# SmartHomeRelaisAktor_0_1.net
KiCad netlist of a schematic drawn in EAGLE
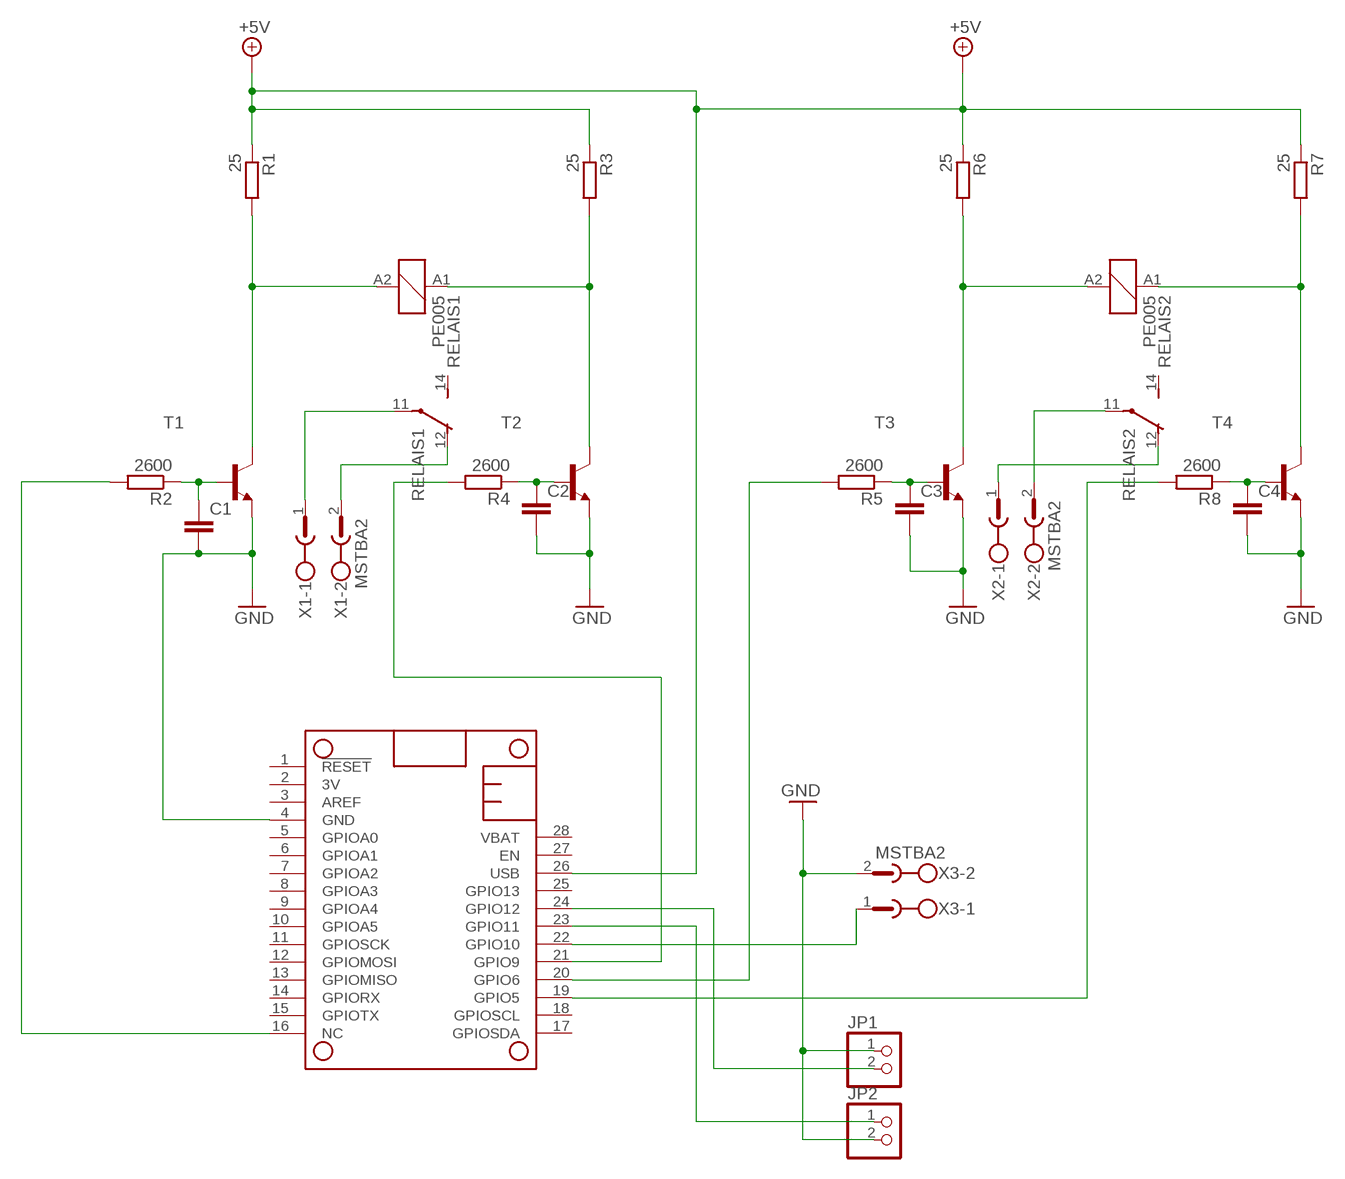
[diagram p0: schematic, sheet 1]

(export (version "E")
  (design (tool "Eeschema 10.0.6"))
  (components
    (comp (ref "C1")
      (value "C-EUC0805")
      (footprint "eagle-import:C0805")
      (libsource (lib "eagle-import") (part "C-EUC0805"))
    )
    (comp (ref "C2")
      (value "C-EUC0805")
      (footprint "eagle-import:C0805")
      (libsource (lib "eagle-import") (part "C-EUC0805"))
    )
    (comp (ref "C3")
      (value "C-EUC0805")
      (footprint "eagle-import:C0805")
      (libsource (lib "eagle-import") (part "C-EUC0805"))
    )
    (comp (ref "C4")
      (value "C-EUC0805")
      (footprint "eagle-import:C0805")
      (libsource (lib "eagle-import") (part "C-EUC0805"))
    )
    (comp (ref "JP1")
      (value "PINHD-1X2")
      (footprint "eagle-import:1X02")
      (libsource (lib "eagle-import") (part "PINHD-1X2"))
    )
    (comp (ref "JP2")
      (value "PINHD-1X2")
      (footprint "eagle-import:1X02")
      (libsource (lib "eagle-import") (part "PINHD-1X2"))
    )
    (comp (ref "MS1")
      (value "FEATHERWING")
      (footprint "eagle-import:FEATHERWING")
      (libsource (lib "eagle-import") (part "FEATHERWING"))
    )
    (comp (ref "R1")
      (value "25")
      (footprint "eagle-import:R0805")
      (libsource (lib "eagle-import") (part "R-EU_R0805"))
    )
    (comp (ref "R2")
      (value "2600")
      (footprint "eagle-import:R0805")
      (libsource (lib "eagle-import") (part "R-EU_R0805"))
    )
    (comp (ref "R3")
      (value "25")
      (footprint "eagle-import:R0805")
      (libsource (lib "eagle-import") (part "R-EU_R0805"))
    )
    (comp (ref "R4")
      (value "2600")
      (footprint "eagle-import:R0805")
      (libsource (lib "eagle-import") (part "R-EU_R0805"))
    )
    (comp (ref "R5")
      (value "2600")
      (footprint "eagle-import:R0805")
      (libsource (lib "eagle-import") (part "R-EU_R0805"))
    )
    (comp (ref "R6")
      (value "25")
      (footprint "eagle-import:R0805")
      (libsource (lib "eagle-import") (part "R-EU_R0805"))
    )
    (comp (ref "R7")
      (value "25")
      (footprint "eagle-import:R0805")
      (libsource (lib "eagle-import") (part "R-EU_R0805"))
    )
    (comp (ref "R8")
      (value "2600")
      (footprint "eagle-import:R0805")
      (libsource (lib "eagle-import") (part "R-EU_R0805"))
    )
    (comp (ref "RELAIS1")
      (value "PE005")
      (footprint "eagle-import:PE")
      (libsource (lib "eagle-import") (part "PE005"))
    )
    (comp (ref "RELAIS2")
      (value "PE005")
      (footprint "eagle-import:PE")
      (libsource (lib "eagle-import") (part "PE005"))
    )
    (comp (ref "T1")
      (value "BC817-16-NPN-SOT23-BEC")
      (footprint "eagle-import:SOT23-BEC")
      (libsource (lib "eagle-import") (part "-NPN-SOT23-BECBC817-16"))
    )
    (comp (ref "T2")
      (value "BC817-16-NPN-SOT23-BEC")
      (footprint "eagle-import:SOT23-BEC")
      (libsource (lib "eagle-import") (part "-NPN-SOT23-BECBC817-16"))
    )
    (comp (ref "T3")
      (value "BC817-16-NPN-SOT23-BEC")
      (footprint "eagle-import:SOT23-BEC")
      (libsource (lib "eagle-import") (part "-NPN-SOT23-BECBC817-16"))
    )
    (comp (ref "T4")
      (value "BC817-16-NPN-SOT23-BEC")
      (footprint "eagle-import:SOT23-BEC")
      (libsource (lib "eagle-import") (part "-NPN-SOT23-BECBC817-16"))
    )
    (comp (ref "X1")
      (value "MSTBA2")
      (footprint "eagle-import:MSTBA2")
      (fields (field (name "MF") "FARNELL") (field (name "MPN") "1757242"))
      (libsource (lib "eagle-import") (part "MSTBA2"))
    )
    (comp (ref "X2")
      (value "MSTBA2")
      (footprint "eagle-import:MSTBA2")
      (fields (field (name "MF") "FARNELL") (field (name "MPN") "1757242"))
      (libsource (lib "eagle-import") (part "MSTBA2"))
    )
    (comp (ref "X3")
      (value "MSTBA2")
      (footprint "eagle-import:MSTBA2")
      (fields (field (name "MF") "FARNELL") (field (name "MPN") "1757242"))
      (libsource (lib "eagle-import") (part "MSTBA2"))
    )
  )
  (nets
    (net (code "1") (name "+5V") (class "Default")
      (node (ref "MS1") (pin "26") (pinfunction "USB_26") (pintype "power_in"))
      (node (ref "R1") (pin "1") (pinfunction "1_1") (pintype "passive"))
      (node (ref "R3") (pin "1") (pinfunction "1_1") (pintype "passive"))
      (node (ref "R6") (pin "1") (pinfunction "1_1") (pintype "passive"))
      (node (ref "R7") (pin "1") (pinfunction "1_1") (pintype "passive"))
    )
    (net (code "2") (name "/3V") (class "Default")
      (node (ref "MS1") (pin "2") (pinfunction "3V_2") (pintype "power_in"))
    )
    (net (code "3") (name "/VBAT") (class "Default")
      (node (ref "MS1") (pin "28") (pinfunction "VBAT_28") (pintype "power_in"))
    )
    (net (code "4") (name "GND") (class "Default")
      (node (ref "C1") (pin "2") (pinfunction "2_2") (pintype "passive"))
      (node (ref "C2") (pin "2") (pinfunction "2_2") (pintype "passive"))
      (node (ref "C3") (pin "2") (pinfunction "2_2") (pintype "passive"))
      (node (ref "C4") (pin "2") (pinfunction "2_2") (pintype "passive"))
      (node (ref "JP1") (pin "1") (pinfunction "1_1") (pintype "passive"))
      (node (ref "JP2") (pin "2") (pinfunction "2_2") (pintype "passive"))
      (node (ref "MS1") (pin "4") (pinfunction "GND_4") (pintype "power_in"))
      (node (ref "T1") (pin "E") (pinfunction "E_E") (pintype "passive"))
      (node (ref "T2") (pin "E") (pinfunction "E_E") (pintype "passive"))
      (node (ref "T3") (pin "E") (pinfunction "E_E") (pintype "passive"))
      (node (ref "T4") (pin "E") (pinfunction "E_E") (pintype "passive"))
      (node (ref "X3") (pin "2") (pinfunction "1_2") (pintype "passive"))
    )
    (net (code "5") (name "Net-(C1-Pad1)") (class "Default")
      (node (ref "C1") (pin "1") (pinfunction "1_1") (pintype "passive"))
      (node (ref "R2") (pin "1") (pinfunction "1_1") (pintype "passive"))
      (node (ref "T1") (pin "B") (pinfunction "B_B") (pintype "passive"))
    )
    (net (code "6") (name "Net-(C2-Pad1)") (class "Default")
      (node (ref "C2") (pin "1") (pinfunction "1_1") (pintype "passive"))
      (node (ref "R4") (pin "1") (pinfunction "1_1") (pintype "passive"))
      (node (ref "T2") (pin "B") (pinfunction "B_B") (pintype "passive"))
    )
    (net (code "7") (name "Net-(C3-Pad1)") (class "Default")
      (node (ref "C3") (pin "1") (pinfunction "1_1") (pintype "passive"))
      (node (ref "R5") (pin "1") (pinfunction "1_1") (pintype "passive"))
      (node (ref "T3") (pin "B") (pinfunction "B_B") (pintype "passive"))
    )
    (net (code "8") (name "Net-(C4-Pad1)") (class "Default")
      (node (ref "C4") (pin "1") (pinfunction "1_1") (pintype "passive"))
      (node (ref "R8") (pin "1") (pinfunction "1_1") (pintype "passive"))
      (node (ref "T4") (pin "B") (pinfunction "B_B") (pintype "passive"))
    )
    (net (code "9") (name "Net-(MS1-GPIO5)") (class "Default")
      (node (ref "MS1") (pin "19") (pinfunction "GPIO5_19") (pintype "bidirectional"))
      (node (ref "R8") (pin "2") (pinfunction "2_2") (pintype "passive"))
    )
    (net (code "10") (name "Net-(MS1-GPIO6)") (class "Default")
      (node (ref "MS1") (pin "20") (pinfunction "GPIO6_20") (pintype "bidirectional"))
      (node (ref "R5") (pin "2") (pinfunction "2_2") (pintype "passive"))
    )
    (net (code "11") (name "Net-(MS1-GPIO9)") (class "Default")
      (node (ref "MS1") (pin "21") (pinfunction "GPIO9_21") (pintype "bidirectional"))
      (node (ref "R4") (pin "2") (pinfunction "2_2") (pintype "passive"))
    )
    (net (code "12") (name "Net-(MS1-GPIO10)") (class "Default")
      (node (ref "MS1") (pin "22") (pinfunction "GPIO10_22") (pintype "bidirectional"))
      (node (ref "X3") (pin "1") (pinfunction "1_1") (pintype "passive"))
    )
    (net (code "13") (name "Net-(MS1-GPIO11)") (class "Default")
      (node (ref "JP2") (pin "1") (pinfunction "1_1") (pintype "passive"))
      (node (ref "MS1") (pin "23") (pinfunction "GPIO11_23") (pintype "bidirectional"))
    )
    (net (code "14") (name "Net-(MS1-GPIO12)") (class "Default")
      (node (ref "JP1") (pin "2") (pinfunction "2_2") (pintype "passive"))
      (node (ref "MS1") (pin "24") (pinfunction "GPIO12_24") (pintype "bidirectional"))
    )
    (net (code "15") (name "Net-(MS1-NC)") (class "Default")
      (node (ref "MS1") (pin "16") (pinfunction "NC_16") (pintype "passive"))
      (node (ref "R2") (pin "2") (pinfunction "2_2") (pintype "passive"))
    )
    (net (code "16") (name "Net-(RELAIS1A-1)") (class "Default")
      (node (ref "R3") (pin "2") (pinfunction "2_2") (pintype "passive"))
      (node (ref "RELAIS1") (pin "A1") (pinfunction "1_A1") (pintype "passive"))
      (node (ref "T2") (pin "C") (pinfunction "C_C") (pintype "passive"))
    )
    (net (code "17") (name "Net-(RELAIS1A-2)") (class "Default")
      (node (ref "R1") (pin "2") (pinfunction "2_2") (pintype "passive"))
      (node (ref "RELAIS1") (pin "A2") (pinfunction "2_A2") (pintype "passive"))
      (node (ref "T1") (pin "C") (pinfunction "C_C") (pintype "passive"))
    )
    (net (code "18") (name "Net-(RELAIS1B-O)") (class "Default")
      (node (ref "RELAIS1") (pin "12") (pinfunction "O_12") (pintype "passive"))
      (node (ref "X1") (pin "2") (pinfunction "1_2") (pintype "passive"))
    )
    (net (code "19") (name "Net-(RELAIS1B-P)") (class "Default")
      (node (ref "RELAIS1") (pin "11") (pinfunction "P_11") (pintype "passive"))
      (node (ref "X1") (pin "1") (pinfunction "1_1") (pintype "passive"))
    )
    (net (code "20") (name "Net-(RELAIS2A-1)") (class "Default")
      (node (ref "R7") (pin "2") (pinfunction "2_2") (pintype "passive"))
      (node (ref "RELAIS2") (pin "A1") (pinfunction "1_A1") (pintype "passive"))
      (node (ref "T4") (pin "C") (pinfunction "C_C") (pintype "passive"))
    )
    (net (code "21") (name "Net-(RELAIS2A-2)") (class "Default")
      (node (ref "R6") (pin "2") (pinfunction "2_2") (pintype "passive"))
      (node (ref "RELAIS2") (pin "A2") (pinfunction "2_A2") (pintype "passive"))
      (node (ref "T3") (pin "C") (pinfunction "C_C") (pintype "passive"))
    )
    (net (code "22") (name "Net-(RELAIS2B-O)") (class "Default")
      (node (ref "RELAIS2") (pin "12") (pinfunction "O_12") (pintype "passive"))
      (node (ref "X2") (pin "1") (pinfunction "1_1") (pintype "passive"))
    )
    (net (code "23") (name "Net-(RELAIS2B-P)") (class "Default")
      (node (ref "RELAIS2") (pin "11") (pinfunction "P_11") (pintype "passive"))
      (node (ref "X2") (pin "2") (pinfunction "1_2") (pintype "passive"))
    )
    (net (code "24") (name "unconnected-(MS1-AREF-Pad3)") (class "Default")
      (node (ref "MS1") (pin "3") (pinfunction "AREF_3") (pintype "passive"))
    )
    (net (code "25") (name "unconnected-(MS1-EN-Pad27)") (class "Default")
      (node (ref "MS1") (pin "27") (pinfunction "EN_27") (pintype "passive"))
    )
    (net (code "26") (name "unconnected-(MS1-GPIO13-Pad25)") (class "Default")
      (node (ref "MS1") (pin "25") (pinfunction "GPIO13_25") (pintype "bidirectional"))
    )
    (net (code "27") (name "unconnected-(MS1-GPIOA0-Pad5)") (class "Default")
      (node (ref "MS1") (pin "5") (pinfunction "GPIOA0_5") (pintype "bidirectional"))
    )
    (net (code "28") (name "unconnected-(MS1-GPIOA1-Pad6)") (class "Default")
      (node (ref "MS1") (pin "6") (pinfunction "GPIOA1_6") (pintype "bidirectional"))
    )
    (net (code "29") (name "unconnected-(MS1-GPIOA2-Pad7)") (class "Default")
      (node (ref "MS1") (pin "7") (pinfunction "GPIOA2_7") (pintype "bidirectional"))
    )
    (net (code "30") (name "unconnected-(MS1-GPIOA3-Pad8)") (class "Default")
      (node (ref "MS1") (pin "8") (pinfunction "GPIOA3_8") (pintype "bidirectional"))
    )
    (net (code "31") (name "unconnected-(MS1-GPIOA4-Pad9)") (class "Default")
      (node (ref "MS1") (pin "9") (pinfunction "GPIOA4_9") (pintype "bidirectional"))
    )
    (net (code "32") (name "unconnected-(MS1-GPIOA5-Pad10)") (class "Default")
      (node (ref "MS1") (pin "10") (pinfunction "GPIOA5_10") (pintype "bidirectional"))
    )
    (net (code "33") (name "unconnected-(MS1-GPIOMISO-Pad13)") (class "Default")
      (node (ref "MS1") (pin "13") (pinfunction "GPIOMISO_13") (pintype "bidirectional"))
    )
    (net (code "34") (name "unconnected-(MS1-GPIOMOSI-Pad12)") (class "Default")
      (node (ref "MS1") (pin "12") (pinfunction "GPIOMOSI_12") (pintype "bidirectional"))
    )
    (net (code "35") (name "unconnected-(MS1-GPIORX-Pad14)") (class "Default")
      (node (ref "MS1") (pin "14") (pinfunction "GPIORX_14") (pintype "bidirectional"))
    )
    (net (code "36") (name "unconnected-(MS1-GPIOSCK-Pad11)") (class "Default")
      (node (ref "MS1") (pin "11") (pinfunction "GPIOSCK_11") (pintype "bidirectional"))
    )
    (net (code "37") (name "unconnected-(MS1-GPIOSCL-Pad18)") (class "Default")
      (node (ref "MS1") (pin "18") (pinfunction "GPIOSCL_18") (pintype "bidirectional"))
    )
    (net (code "38") (name "unconnected-(MS1-GPIOSDA-Pad17)") (class "Default")
      (node (ref "MS1") (pin "17") (pinfunction "GPIOSDA_17") (pintype "bidirectional"))
    )
    (net (code "39") (name "unconnected-(MS1-GPIOTX-Pad15)") (class "Default")
      (node (ref "MS1") (pin "15") (pinfunction "GPIOTX_15") (pintype "bidirectional"))
    )
    (net (code "40") (name "unconnected-(MS1-~{RESET}-Pad1)") (class "Default")
      (node (ref "MS1") (pin "1") (pinfunction "~{RESET}_1") (pintype "input"))
    )
    (net (code "41") (name "unconnected-(RELAIS1B-S-Pad14)") (class "Default")
      (node (ref "RELAIS1") (pin "14") (pinfunction "S_14") (pintype "passive"))
    )
    (net (code "42") (name "unconnected-(RELAIS2B-S-Pad14)") (class "Default")
      (node (ref "RELAIS2") (pin "14") (pinfunction "S_14") (pintype "passive"))
    )
  )
)
